# LCD_BackPack_wider.net
KiCad netlist of a schematic drawn in EAGLE
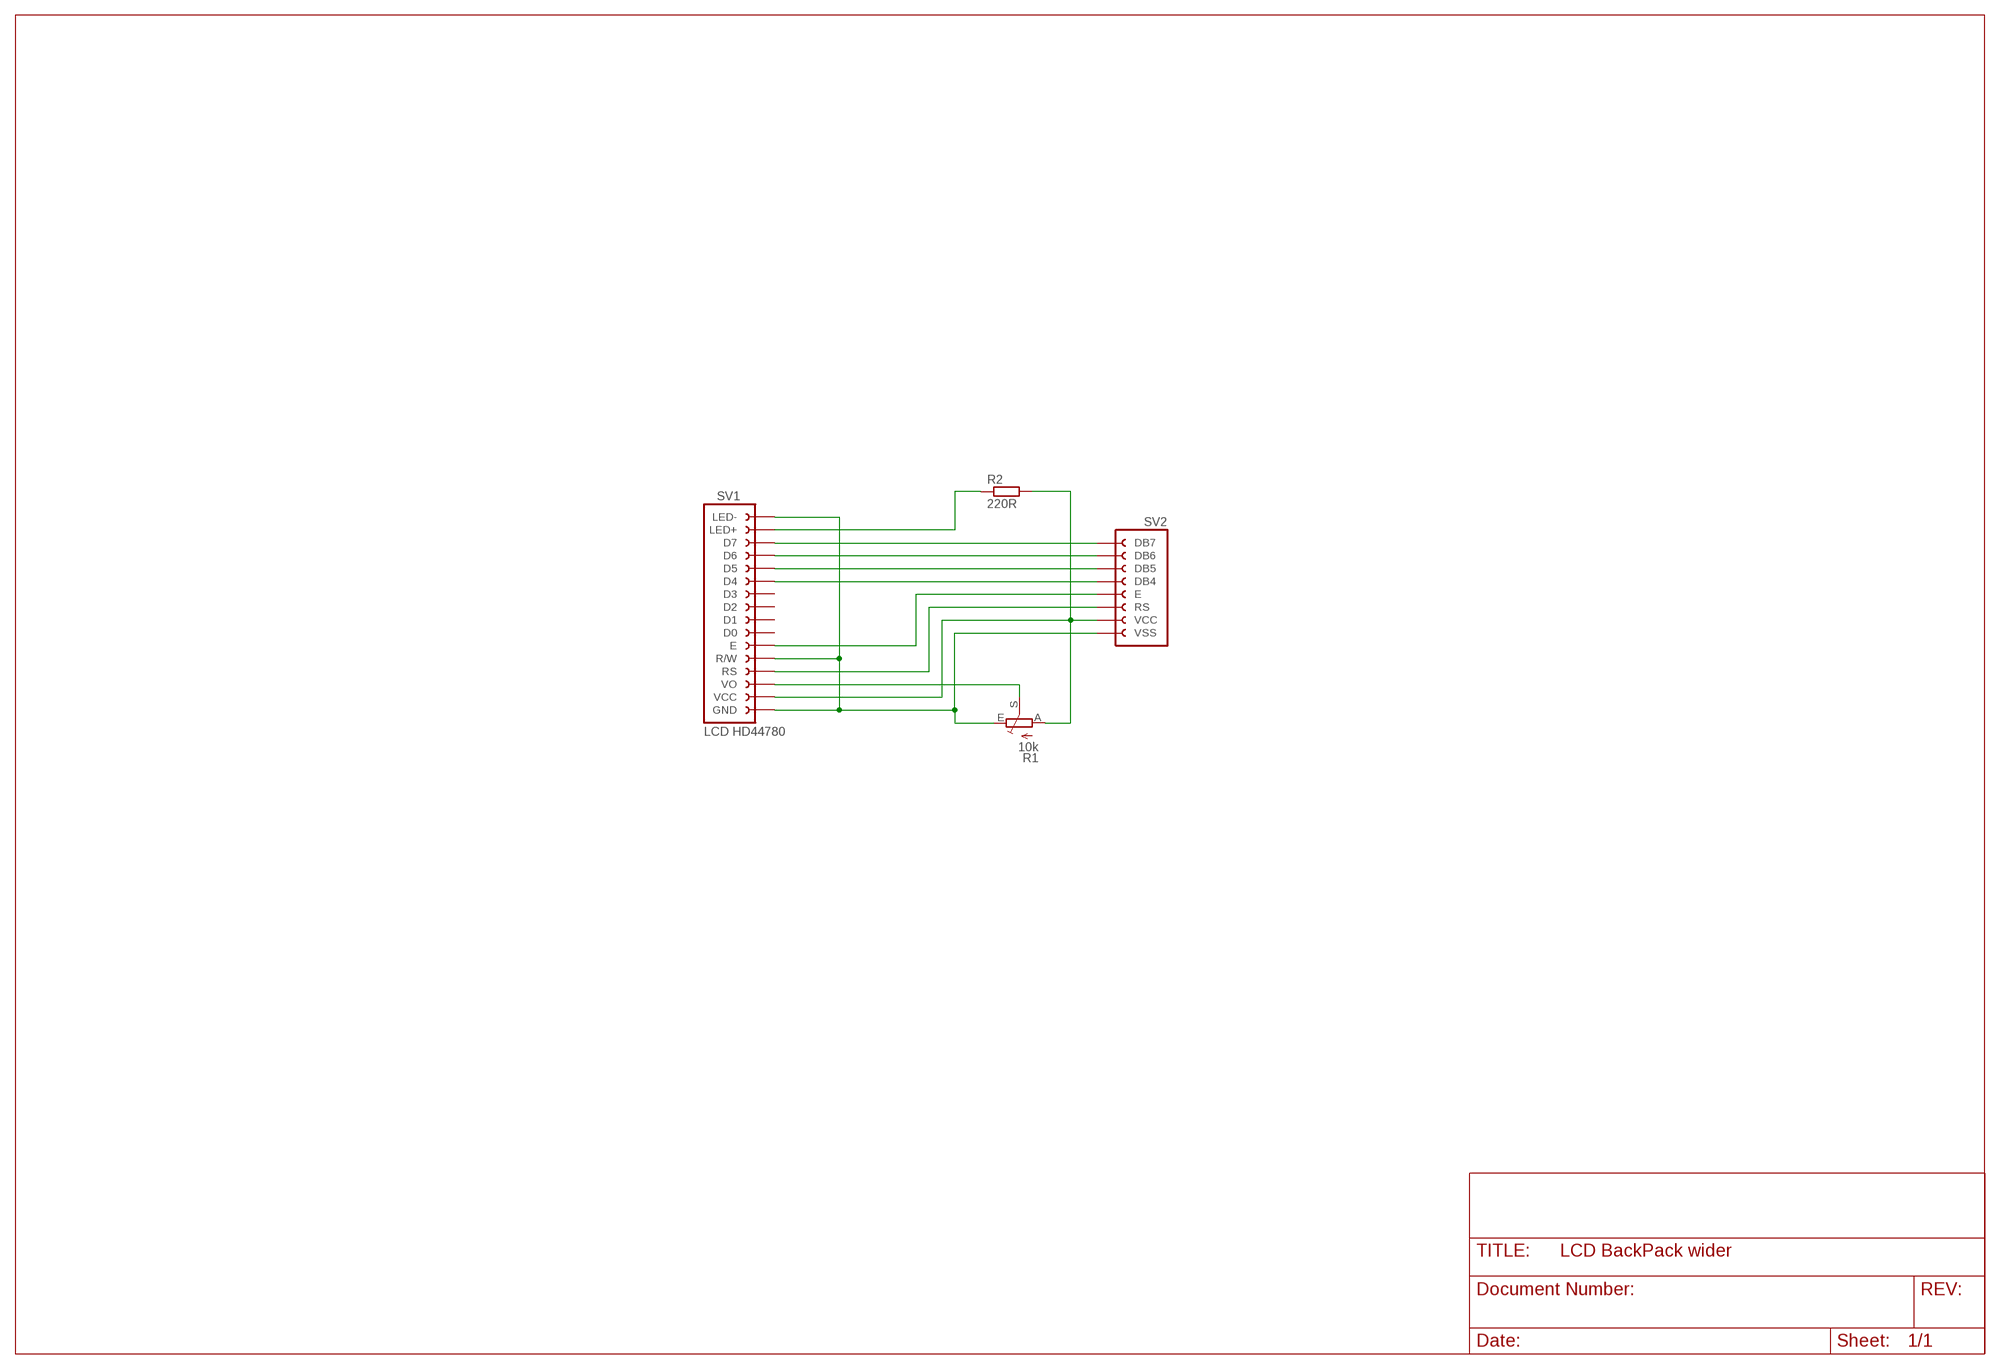
[diagram p0: schematic, sheet 1]

(export (version "E")
  (design (tool "Eeschema 10.0.6"))
  (components
    (comp (ref "R1")
      (value "10k")
      (footprint "eagle-import:CA6V")
      (libsource (lib "eagle-import") (part "POTENTIOMETER_CA6VCA6V"))
    )
    (comp (ref "R2")
      (value "220R")
      (footprint "eagle-import:0204_7")
      (libsource (lib "eagle-import") (part "R-EU_0204/7"))
    )
    (comp (ref "SV1")
      (value "LCD-HD44780-16-PIN_FEMALE_HEADER")
      (footprint "eagle-import:LCD-HD44780-16-PIN_FEMALE_HEADER")
      (libsource (lib "eagle-import") (part "LCD-HD44780-16-PIN_FEMALE_HEADER"))
    )
    (comp (ref "SV2")
      (value "LCD-CONTROL_8-PIN_FEMALE_HEADER")
      (footprint "eagle-import:LCD-CONTROL_8-PIN_FEMALE_HEADER")
      (libsource (lib "eagle-import") (part "LCD-CONTROL_8-PIN_FEMALE_HEADER"))
    )
  )
  (nets
    (net (code "1") (name "Net-(R1-PadA)") (class "Default")
      (node (ref "R1") (pin "A") (pinfunction "A_A") (pintype "passive"))
      (node (ref "R2") (pin "2") (pinfunction "2_2") (pintype "passive"))
      (node (ref "SV1") (pin "VCC") (pinfunction "VCC_VCC") (pintype "passive"))
      (node (ref "SV2") (pin "VCC") (pinfunction "VCC_VCC") (pintype "passive"))
    )
    (net (code "2") (name "Net-(R1-PadE)") (class "Default")
      (node (ref "R1") (pin "E") (pinfunction "E_E") (pintype "passive"))
      (node (ref "SV1") (pin "GND") (pinfunction "GND_GND") (pintype "passive"))
      (node (ref "SV1") (pin "LED-") (pinfunction "LED-_LED-") (pintype "passive"))
      (node (ref "SV1") (pin "R/W") (pinfunction "R/W_R/W") (pintype "passive"))
      (node (ref "SV2") (pin "VSS") (pinfunction "VSS_VSS") (pintype "passive"))
    )
    (net (code "3") (name "Net-(R1-PadS)") (class "Default")
      (node (ref "R1") (pin "S") (pinfunction "S_S") (pintype "passive"))
      (node (ref "SV1") (pin "VO") (pinfunction "VO_VO") (pintype "passive"))
    )
    (net (code "4") (name "Net-(R2-Pad1)") (class "Default")
      (node (ref "R2") (pin "1") (pinfunction "1_1") (pintype "passive"))
      (node (ref "SV1") (pin "LED+") (pinfunction "LED+_LED+") (pintype "passive"))
    )
    (net (code "5") (name "Net-(SV1-PadD4)") (class "Default")
      (node (ref "SV1") (pin "D4") (pinfunction "D4_D4") (pintype "passive"))
      (node (ref "SV2") (pin "DB4") (pinfunction "DB4_DB4") (pintype "passive"))
    )
    (net (code "6") (name "Net-(SV1-PadD5)") (class "Default")
      (node (ref "SV1") (pin "D5") (pinfunction "D5_D5") (pintype "passive"))
      (node (ref "SV2") (pin "DB5") (pinfunction "DB5_DB5") (pintype "passive"))
    )
    (net (code "7") (name "Net-(SV1-PadD6)") (class "Default")
      (node (ref "SV1") (pin "D6") (pinfunction "D6_D6") (pintype "passive"))
      (node (ref "SV2") (pin "DB6") (pinfunction "DB6_DB6") (pintype "passive"))
    )
    (net (code "8") (name "Net-(SV1-PadD7)") (class "Default")
      (node (ref "SV1") (pin "D7") (pinfunction "D7_D7") (pintype "passive"))
      (node (ref "SV2") (pin "DB7") (pinfunction "DB7_DB7") (pintype "passive"))
    )
    (net (code "9") (name "Net-(SV1-PadE)") (class "Default")
      (node (ref "SV1") (pin "E") (pinfunction "E_E") (pintype "passive"))
      (node (ref "SV2") (pin "E") (pinfunction "E_E") (pintype "passive"))
    )
    (net (code "10") (name "Net-(SV1-PadRS)") (class "Default")
      (node (ref "SV1") (pin "RS") (pinfunction "RS_RS") (pintype "passive"))
      (node (ref "SV2") (pin "RS") (pinfunction "RS_RS") (pintype "passive"))
    )
    (net (code "11") (name "unconnected-(SV1-PadD0)") (class "Default")
      (node (ref "SV1") (pin "D0") (pinfunction "D0_D0") (pintype "passive"))
    )
    (net (code "12") (name "unconnected-(SV1-PadD1)") (class "Default")
      (node (ref "SV1") (pin "D1") (pinfunction "D1_D1") (pintype "passive"))
    )
    (net (code "13") (name "unconnected-(SV1-PadD2)") (class "Default")
      (node (ref "SV1") (pin "D2") (pinfunction "D2_D2") (pintype "passive"))
    )
    (net (code "14") (name "unconnected-(SV1-PadD3)") (class "Default")
      (node (ref "SV1") (pin "D3") (pinfunction "D3_D3") (pintype "passive"))
    )
  )
)
